# Floppy_Shield.net
KiCad netlist of a schematic drawn in EAGLE
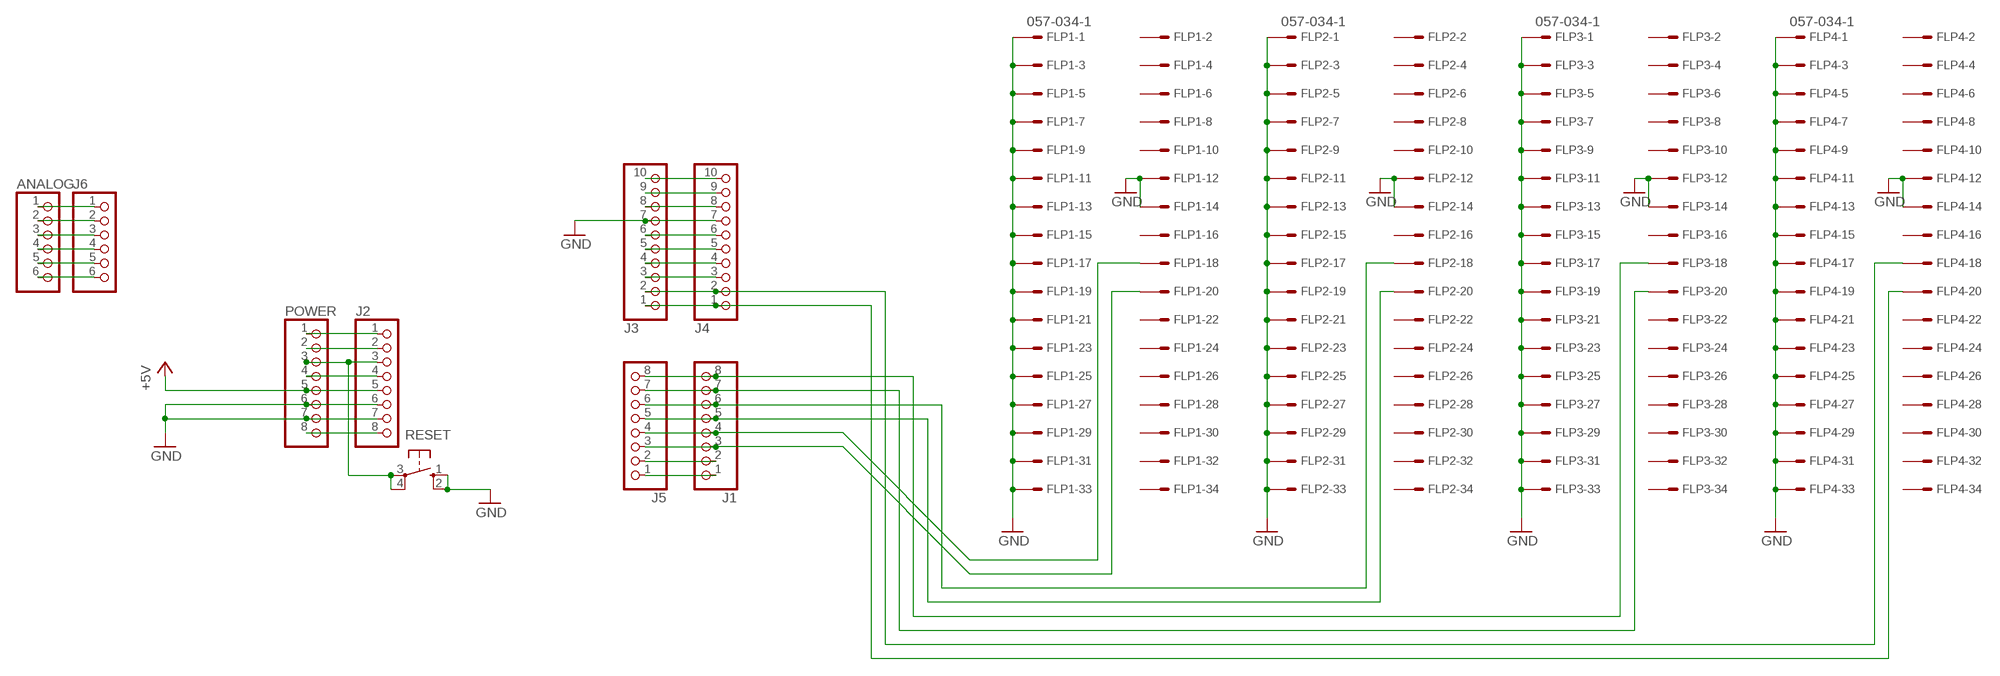
[diagram p0: schematic, sheet 1]

(export (version "E")
  (design (tool "Eeschema 10.0.6"))
  (components
    (comp (ref "ANALOG")
      (value "PINHD-1X6")
      (footprint "eagle-import:1X06")
      (libsource (lib "eagle-import") (part "PINHD-1X6"))
    )
    (comp (ref "FLP1")
      (value "057-034-1")
      (footprint "eagle-import:057-034-1")
      (libsource (lib "eagle-import") (part "057-034-1"))
    )
    (comp (ref "FLP2")
      (value "057-034-1")
      (footprint "eagle-import:057-034-1")
      (libsource (lib "eagle-import") (part "057-034-1"))
    )
    (comp (ref "FLP3")
      (value "057-034-1")
      (footprint "eagle-import:057-034-1")
      (libsource (lib "eagle-import") (part "057-034-1"))
    )
    (comp (ref "FLP4")
      (value "057-034-1")
      (footprint "eagle-import:057-034-1")
      (libsource (lib "eagle-import") (part "057-034-1"))
    )
    (comp (ref "J1")
      (value "PINHD-1X8TH")
      (footprint "eagle-import:1X08-TH")
      (libsource (lib "eagle-import") (part "PINHD-1X8TH"))
    )
    (comp (ref "J2")
      (value "PINHD-1X8TH")
      (footprint "eagle-import:1X08-TH")
      (libsource (lib "eagle-import") (part "PINHD-1X8TH"))
    )
    (comp (ref "J3")
      (value "PINHD-1X10TH")
      (footprint "eagle-import:1X10-TH")
      (libsource (lib "eagle-import") (part "PINHD-1X10TH"))
    )
    (comp (ref "J4")
      (value "PINHD-1X10TH")
      (footprint "eagle-import:1X10-TH")
      (libsource (lib "eagle-import") (part "PINHD-1X10TH"))
    )
    (comp (ref "J5")
      (value "PINHD-1X8TH")
      (footprint "eagle-import:1X08-TH")
      (libsource (lib "eagle-import") (part "PINHD-1X8TH"))
    )
    (comp (ref "J6")
      (value "PINHD-1X6")
      (footprint "eagle-import:1X06")
      (libsource (lib "eagle-import") (part "PINHD-1X6"))
    )
    (comp (ref "POWER")
      (value "PINHD-1X8TH")
      (footprint "eagle-import:1X08-TH")
      (libsource (lib "eagle-import") (part "PINHD-1X8TH"))
    )
    (comp (ref "RESET")
      (value "10-XX")
      (footprint "eagle-import:B3F-10XX")
      (libsource (lib "eagle-import") (part "10-XX"))
    )
  )
  (nets
    (net (code "1") (name "+5V") (class "Default")
      (node (ref "J2") (pin "5") (pinfunction "5_5") (pintype "passive"))
      (node (ref "POWER") (pin "5") (pinfunction "5_5") (pintype "passive"))
    )
    (net (code "2") (name "GND") (class "Default")
      (node (ref "FLP1") (pin "1") (pinfunction "S_1") (pintype "passive"))
      (node (ref "FLP1") (pin "11") (pinfunction "S_11") (pintype "passive"))
      (node (ref "FLP1") (pin "12") (pinfunction "S_12") (pintype "passive"))
      (node (ref "FLP1") (pin "13") (pinfunction "S_13") (pintype "passive"))
      (node (ref "FLP1") (pin "14") (pinfunction "S_14") (pintype "passive"))
      (node (ref "FLP1") (pin "15") (pinfunction "S_15") (pintype "passive"))
      (node (ref "FLP1") (pin "17") (pinfunction "S_17") (pintype "passive"))
      (node (ref "FLP1") (pin "19") (pinfunction "S_19") (pintype "passive"))
      (node (ref "FLP1") (pin "21") (pinfunction "S_21") (pintype "passive"))
      (node (ref "FLP1") (pin "23") (pinfunction "S_23") (pintype "passive"))
      (node (ref "FLP1") (pin "25") (pinfunction "S_25") (pintype "passive"))
      (node (ref "FLP1") (pin "27") (pinfunction "S_27") (pintype "passive"))
      (node (ref "FLP1") (pin "29") (pinfunction "S_29") (pintype "passive"))
      (node (ref "FLP1") (pin "3") (pinfunction "S_3") (pintype "passive"))
      (node (ref "FLP1") (pin "31") (pinfunction "S_31") (pintype "passive"))
      (node (ref "FLP1") (pin "33") (pinfunction "S_33") (pintype "passive"))
      (node (ref "FLP1") (pin "5") (pinfunction "S_5") (pintype "passive"))
      (node (ref "FLP1") (pin "7") (pinfunction "S_7") (pintype "passive"))
      (node (ref "FLP1") (pin "9") (pinfunction "S_9") (pintype "passive"))
      (node (ref "FLP2") (pin "1") (pinfunction "S_1") (pintype "passive"))
      (node (ref "FLP2") (pin "11") (pinfunction "S_11") (pintype "passive"))
      (node (ref "FLP2") (pin "12") (pinfunction "S_12") (pintype "passive"))
      (node (ref "FLP2") (pin "13") (pinfunction "S_13") (pintype "passive"))
      (node (ref "FLP2") (pin "14") (pinfunction "S_14") (pintype "passive"))
      (node (ref "FLP2") (pin "15") (pinfunction "S_15") (pintype "passive"))
      (node (ref "FLP2") (pin "17") (pinfunction "S_17") (pintype "passive"))
      (node (ref "FLP2") (pin "19") (pinfunction "S_19") (pintype "passive"))
      (node (ref "FLP2") (pin "21") (pinfunction "S_21") (pintype "passive"))
      (node (ref "FLP2") (pin "23") (pinfunction "S_23") (pintype "passive"))
      (node (ref "FLP2") (pin "25") (pinfunction "S_25") (pintype "passive"))
      (node (ref "FLP2") (pin "27") (pinfunction "S_27") (pintype "passive"))
      (node (ref "FLP2") (pin "29") (pinfunction "S_29") (pintype "passive"))
      (node (ref "FLP2") (pin "3") (pinfunction "S_3") (pintype "passive"))
      (node (ref "FLP2") (pin "31") (pinfunction "S_31") (pintype "passive"))
      (node (ref "FLP2") (pin "33") (pinfunction "S_33") (pintype "passive"))
      (node (ref "FLP2") (pin "5") (pinfunction "S_5") (pintype "passive"))
      (node (ref "FLP2") (pin "7") (pinfunction "S_7") (pintype "passive"))
      (node (ref "FLP2") (pin "9") (pinfunction "S_9") (pintype "passive"))
      (node (ref "FLP3") (pin "1") (pinfunction "S_1") (pintype "passive"))
      (node (ref "FLP3") (pin "11") (pinfunction "S_11") (pintype "passive"))
      (node (ref "FLP3") (pin "12") (pinfunction "S_12") (pintype "passive"))
      (node (ref "FLP3") (pin "13") (pinfunction "S_13") (pintype "passive"))
      (node (ref "FLP3") (pin "14") (pinfunction "S_14") (pintype "passive"))
      (node (ref "FLP3") (pin "15") (pinfunction "S_15") (pintype "passive"))
      (node (ref "FLP3") (pin "17") (pinfunction "S_17") (pintype "passive"))
      (node (ref "FLP3") (pin "19") (pinfunction "S_19") (pintype "passive"))
      (node (ref "FLP3") (pin "21") (pinfunction "S_21") (pintype "passive"))
      (node (ref "FLP3") (pin "23") (pinfunction "S_23") (pintype "passive"))
      (node (ref "FLP3") (pin "25") (pinfunction "S_25") (pintype "passive"))
      (node (ref "FLP3") (pin "27") (pinfunction "S_27") (pintype "passive"))
      (node (ref "FLP3") (pin "29") (pinfunction "S_29") (pintype "passive"))
      (node (ref "FLP3") (pin "3") (pinfunction "S_3") (pintype "passive"))
      (node (ref "FLP3") (pin "31") (pinfunction "S_31") (pintype "passive"))
      (node (ref "FLP3") (pin "33") (pinfunction "S_33") (pintype "passive"))
      (node (ref "FLP3") (pin "5") (pinfunction "S_5") (pintype "passive"))
      (node (ref "FLP3") (pin "7") (pinfunction "S_7") (pintype "passive"))
      (node (ref "FLP3") (pin "9") (pinfunction "S_9") (pintype "passive"))
      (node (ref "FLP4") (pin "1") (pinfunction "S_1") (pintype "passive"))
      (node (ref "FLP4") (pin "11") (pinfunction "S_11") (pintype "passive"))
      (node (ref "FLP4") (pin "12") (pinfunction "S_12") (pintype "passive"))
      (node (ref "FLP4") (pin "13") (pinfunction "S_13") (pintype "passive"))
      (node (ref "FLP4") (pin "14") (pinfunction "S_14") (pintype "passive"))
      (node (ref "FLP4") (pin "15") (pinfunction "S_15") (pintype "passive"))
      (node (ref "FLP4") (pin "17") (pinfunction "S_17") (pintype "passive"))
      (node (ref "FLP4") (pin "19") (pinfunction "S_19") (pintype "passive"))
      (node (ref "FLP4") (pin "21") (pinfunction "S_21") (pintype "passive"))
      (node (ref "FLP4") (pin "23") (pinfunction "S_23") (pintype "passive"))
      (node (ref "FLP4") (pin "25") (pinfunction "S_25") (pintype "passive"))
      (node (ref "FLP4") (pin "27") (pinfunction "S_27") (pintype "passive"))
      (node (ref "FLP4") (pin "29") (pinfunction "S_29") (pintype "passive"))
      (node (ref "FLP4") (pin "3") (pinfunction "S_3") (pintype "passive"))
      (node (ref "FLP4") (pin "31") (pinfunction "S_31") (pintype "passive"))
      (node (ref "FLP4") (pin "33") (pinfunction "S_33") (pintype "passive"))
      (node (ref "FLP4") (pin "5") (pinfunction "S_5") (pintype "passive"))
      (node (ref "FLP4") (pin "7") (pinfunction "S_7") (pintype "passive"))
      (node (ref "FLP4") (pin "9") (pinfunction "S_9") (pintype "passive"))
      (node (ref "J2") (pin "6") (pinfunction "6_6") (pintype "passive"))
      (node (ref "J2") (pin "7") (pinfunction "7_7") (pintype "passive"))
      (node (ref "J3") (pin "7") (pinfunction "7_7") (pintype "passive"))
      (node (ref "J4") (pin "7") (pinfunction "7_7") (pintype "passive"))
      (node (ref "POWER") (pin "6") (pinfunction "6_6") (pintype "passive"))
      (node (ref "POWER") (pin "7") (pinfunction "7_7") (pintype "passive"))
      (node (ref "RESET") (pin "1") (pinfunction "S_1") (pintype "passive"))
      (node (ref "RESET") (pin "2") (pinfunction "S1_2") (pintype "passive"))
    )
    (net (code "3") (name "Net-(ANALOG-Pad1)") (class "Default")
      (node (ref "ANALOG") (pin "1") (pinfunction "1_1") (pintype "passive"))
      (node (ref "J6") (pin "1") (pinfunction "1_1") (pintype "passive"))
    )
    (net (code "4") (name "Net-(ANALOG-Pad2)") (class "Default")
      (node (ref "ANALOG") (pin "2") (pinfunction "2_2") (pintype "passive"))
      (node (ref "J6") (pin "2") (pinfunction "2_2") (pintype "passive"))
    )
    (net (code "5") (name "Net-(ANALOG-Pad3)") (class "Default")
      (node (ref "ANALOG") (pin "3") (pinfunction "3_3") (pintype "passive"))
      (node (ref "J6") (pin "3") (pinfunction "3_3") (pintype "passive"))
    )
    (net (code "6") (name "Net-(ANALOG-Pad4)") (class "Default")
      (node (ref "ANALOG") (pin "4") (pinfunction "4_4") (pintype "passive"))
      (node (ref "J6") (pin "4") (pinfunction "4_4") (pintype "passive"))
    )
    (net (code "7") (name "Net-(ANALOG-Pad5)") (class "Default")
      (node (ref "ANALOG") (pin "5") (pinfunction "5_5") (pintype "passive"))
      (node (ref "J6") (pin "5") (pinfunction "5_5") (pintype "passive"))
    )
    (net (code "8") (name "Net-(ANALOG-Pad6)") (class "Default")
      (node (ref "ANALOG") (pin "6") (pinfunction "6_6") (pintype "passive"))
      (node (ref "J6") (pin "6") (pinfunction "6_6") (pintype "passive"))
    )
    (net (code "9") (name "Net-(FLP1J-S)") (class "Default")
      (node (ref "FLP1") (pin "18") (pinfunction "S_18") (pintype "passive"))
      (node (ref "J1") (pin "4") (pinfunction "4_4") (pintype "passive"))
      (node (ref "J5") (pin "4") (pinfunction "4_4") (pintype "passive"))
    )
    (net (code "10") (name "Net-(FLP1M-S)") (class "Default")
      (node (ref "FLP1") (pin "20") (pinfunction "S_20") (pintype "passive"))
      (node (ref "J1") (pin "3") (pinfunction "3_3") (pintype "passive"))
      (node (ref "J5") (pin "3") (pinfunction "3_3") (pintype "passive"))
    )
    (net (code "11") (name "Net-(FLP2J-S)") (class "Default")
      (node (ref "FLP2") (pin "18") (pinfunction "S_18") (pintype "passive"))
      (node (ref "J1") (pin "6") (pinfunction "6_6") (pintype "passive"))
      (node (ref "J5") (pin "6") (pinfunction "6_6") (pintype "passive"))
    )
    (net (code "12") (name "Net-(FLP2M-S)") (class "Default")
      (node (ref "FLP2") (pin "20") (pinfunction "S_20") (pintype "passive"))
      (node (ref "J1") (pin "5") (pinfunction "5_5") (pintype "passive"))
      (node (ref "J5") (pin "5") (pinfunction "5_5") (pintype "passive"))
    )
    (net (code "13") (name "Net-(FLP3J-S)") (class "Default")
      (node (ref "FLP3") (pin "18") (pinfunction "S_18") (pintype "passive"))
      (node (ref "J1") (pin "8") (pinfunction "8_8") (pintype "passive"))
      (node (ref "J5") (pin "8") (pinfunction "8_8") (pintype "passive"))
    )
    (net (code "14") (name "Net-(FLP3M-S)") (class "Default")
      (node (ref "FLP3") (pin "20") (pinfunction "S_20") (pintype "passive"))
      (node (ref "J1") (pin "7") (pinfunction "7_7") (pintype "passive"))
      (node (ref "J5") (pin "7") (pinfunction "7_7") (pintype "passive"))
    )
    (net (code "15") (name "Net-(FLP4J-S)") (class "Default")
      (node (ref "FLP4") (pin "18") (pinfunction "S_18") (pintype "passive"))
      (node (ref "J3") (pin "2") (pinfunction "2_2") (pintype "passive"))
      (node (ref "J4") (pin "2") (pinfunction "2_2") (pintype "passive"))
    )
    (net (code "16") (name "Net-(FLP4M-S)") (class "Default")
      (node (ref "FLP4") (pin "20") (pinfunction "S_20") (pintype "passive"))
      (node (ref "J3") (pin "1") (pinfunction "1_1") (pintype "passive"))
      (node (ref "J4") (pin "1") (pinfunction "1_1") (pintype "passive"))
    )
    (net (code "17") (name "Net-(J1-Pad1)") (class "Default")
      (node (ref "J1") (pin "1") (pinfunction "1_1") (pintype "passive"))
      (node (ref "J5") (pin "1") (pinfunction "1_1") (pintype "passive"))
    )
    (net (code "18") (name "Net-(J1-Pad2)") (class "Default")
      (node (ref "J1") (pin "2") (pinfunction "2_2") (pintype "passive"))
      (node (ref "J5") (pin "2") (pinfunction "2_2") (pintype "passive"))
    )
    (net (code "19") (name "Net-(J2-Pad1)") (class "Default")
      (node (ref "J2") (pin "1") (pinfunction "1_1") (pintype "passive"))
      (node (ref "POWER") (pin "1") (pinfunction "1_1") (pintype "passive"))
    )
    (net (code "20") (name "Net-(J2-Pad2)") (class "Default")
      (node (ref "J2") (pin "2") (pinfunction "2_2") (pintype "passive"))
      (node (ref "POWER") (pin "2") (pinfunction "2_2") (pintype "passive"))
    )
    (net (code "21") (name "Net-(J2-Pad4)") (class "Default")
      (node (ref "J2") (pin "4") (pinfunction "4_4") (pintype "passive"))
      (node (ref "POWER") (pin "4") (pinfunction "4_4") (pintype "passive"))
    )
    (net (code "22") (name "Net-(J2-Pad8)") (class "Default")
      (node (ref "J2") (pin "8") (pinfunction "8_8") (pintype "passive"))
      (node (ref "POWER") (pin "8") (pinfunction "8_8") (pintype "passive"))
    )
    (net (code "23") (name "Net-(J3-Pad3)") (class "Default")
      (node (ref "J3") (pin "3") (pinfunction "3_3") (pintype "passive"))
      (node (ref "J4") (pin "3") (pinfunction "3_3") (pintype "passive"))
    )
    (net (code "24") (name "Net-(J3-Pad4)") (class "Default")
      (node (ref "J3") (pin "4") (pinfunction "4_4") (pintype "passive"))
      (node (ref "J4") (pin "4") (pinfunction "4_4") (pintype "passive"))
    )
    (net (code "25") (name "Net-(J3-Pad5)") (class "Default")
      (node (ref "J3") (pin "5") (pinfunction "5_5") (pintype "passive"))
      (node (ref "J4") (pin "5") (pinfunction "5_5") (pintype "passive"))
    )
    (net (code "26") (name "Net-(J3-Pad6)") (class "Default")
      (node (ref "J3") (pin "6") (pinfunction "6_6") (pintype "passive"))
      (node (ref "J4") (pin "6") (pinfunction "6_6") (pintype "passive"))
    )
    (net (code "27") (name "Net-(J3-Pad8)") (class "Default")
      (node (ref "J3") (pin "8") (pinfunction "8_8") (pintype "passive"))
      (node (ref "J4") (pin "8") (pinfunction "8_8") (pintype "passive"))
    )
    (net (code "28") (name "Net-(J3-Pad9)") (class "Default")
      (node (ref "J3") (pin "9") (pinfunction "9_9") (pintype "passive"))
      (node (ref "J4") (pin "9") (pinfunction "9_9") (pintype "passive"))
    )
    (net (code "29") (name "Net-(J3-Pad10)") (class "Default")
      (node (ref "J3") (pin "10") (pinfunction "10_10") (pintype "passive"))
      (node (ref "J4") (pin "10") (pinfunction "10_10") (pintype "passive"))
    )
    (net (code "30") (name "Net-(RESET-P)") (class "Default")
      (node (ref "J2") (pin "3") (pinfunction "3_3") (pintype "passive"))
      (node (ref "POWER") (pin "3") (pinfunction "3_3") (pintype "passive"))
      (node (ref "RESET") (pin "3") (pinfunction "P_3") (pintype "passive"))
      (node (ref "RESET") (pin "4") (pinfunction "P1_4") (pintype "passive"))
    )
    (net (code "31") (name "unconnected-(FLP1AB-S-Pad34)") (class "Default")
      (node (ref "FLP1") (pin "34") (pinfunction "S_34") (pintype "passive"))
    )
    (net (code "32") (name "unconnected-(FLP1AC-S-Pad4)") (class "Default")
      (node (ref "FLP1") (pin "4") (pinfunction "S_4") (pintype "passive"))
    )
    (net (code "33") (name "unconnected-(FLP1AE-S-Pad6)") (class "Default")
      (node (ref "FLP1") (pin "6") (pinfunction "S_6") (pintype "passive"))
    )
    (net (code "34") (name "unconnected-(FLP1AG-S-Pad8)") (class "Default")
      (node (ref "FLP1") (pin "8") (pinfunction "S_8") (pintype "passive"))
    )
    (net (code "35") (name "unconnected-(FLP1B-S-Pad10)") (class "Default")
      (node (ref "FLP1") (pin "10") (pinfunction "S_10") (pintype "passive"))
    )
    (net (code "36") (name "unconnected-(FLP1H-S-Pad16)") (class "Default")
      (node (ref "FLP1") (pin "16") (pinfunction "S_16") (pintype "passive"))
    )
    (net (code "37") (name "unconnected-(FLP1L-S-Pad2)") (class "Default")
      (node (ref "FLP1") (pin "2") (pinfunction "S_2") (pintype "passive"))
    )
    (net (code "38") (name "unconnected-(FLP1O-S-Pad22)") (class "Default")
      (node (ref "FLP1") (pin "22") (pinfunction "S_22") (pintype "passive"))
    )
    (net (code "39") (name "unconnected-(FLP1Q-S-Pad24)") (class "Default")
      (node (ref "FLP1") (pin "24") (pinfunction "S_24") (pintype "passive"))
    )
    (net (code "40") (name "unconnected-(FLP1S-S-Pad26)") (class "Default")
      (node (ref "FLP1") (pin "26") (pinfunction "S_26") (pintype "passive"))
    )
    (net (code "41") (name "unconnected-(FLP1U-S-Pad28)") (class "Default")
      (node (ref "FLP1") (pin "28") (pinfunction "S_28") (pintype "passive"))
    )
    (net (code "42") (name "unconnected-(FLP1X-S-Pad30)") (class "Default")
      (node (ref "FLP1") (pin "30") (pinfunction "S_30") (pintype "passive"))
    )
    (net (code "43") (name "unconnected-(FLP1Z-S-Pad32)") (class "Default")
      (node (ref "FLP1") (pin "32") (pinfunction "S_32") (pintype "passive"))
    )
    (net (code "44") (name "unconnected-(FLP2AB-S-Pad34)") (class "Default")
      (node (ref "FLP2") (pin "34") (pinfunction "S_34") (pintype "passive"))
    )
    (net (code "45") (name "unconnected-(FLP2AC-S-Pad4)") (class "Default")
      (node (ref "FLP2") (pin "4") (pinfunction "S_4") (pintype "passive"))
    )
    (net (code "46") (name "unconnected-(FLP2AE-S-Pad6)") (class "Default")
      (node (ref "FLP2") (pin "6") (pinfunction "S_6") (pintype "passive"))
    )
    (net (code "47") (name "unconnected-(FLP2AG-S-Pad8)") (class "Default")
      (node (ref "FLP2") (pin "8") (pinfunction "S_8") (pintype "passive"))
    )
    (net (code "48") (name "unconnected-(FLP2B-S-Pad10)") (class "Default")
      (node (ref "FLP2") (pin "10") (pinfunction "S_10") (pintype "passive"))
    )
    (net (code "49") (name "unconnected-(FLP2H-S-Pad16)") (class "Default")
      (node (ref "FLP2") (pin "16") (pinfunction "S_16") (pintype "passive"))
    )
    (net (code "50") (name "unconnected-(FLP2L-S-Pad2)") (class "Default")
      (node (ref "FLP2") (pin "2") (pinfunction "S_2") (pintype "passive"))
    )
    (net (code "51") (name "unconnected-(FLP2O-S-Pad22)") (class "Default")
      (node (ref "FLP2") (pin "22") (pinfunction "S_22") (pintype "passive"))
    )
    (net (code "52") (name "unconnected-(FLP2Q-S-Pad24)") (class "Default")
      (node (ref "FLP2") (pin "24") (pinfunction "S_24") (pintype "passive"))
    )
    (net (code "53") (name "unconnected-(FLP2S-S-Pad26)") (class "Default")
      (node (ref "FLP2") (pin "26") (pinfunction "S_26") (pintype "passive"))
    )
    (net (code "54") (name "unconnected-(FLP2U-S-Pad28)") (class "Default")
      (node (ref "FLP2") (pin "28") (pinfunction "S_28") (pintype "passive"))
    )
    (net (code "55") (name "unconnected-(FLP2X-S-Pad30)") (class "Default")
      (node (ref "FLP2") (pin "30") (pinfunction "S_30") (pintype "passive"))
    )
    (net (code "56") (name "unconnected-(FLP2Z-S-Pad32)") (class "Default")
      (node (ref "FLP2") (pin "32") (pinfunction "S_32") (pintype "passive"))
    )
    (net (code "57") (name "unconnected-(FLP3AB-S-Pad34)") (class "Default")
      (node (ref "FLP3") (pin "34") (pinfunction "S_34") (pintype "passive"))
    )
    (net (code "58") (name "unconnected-(FLP3AC-S-Pad4)") (class "Default")
      (node (ref "FLP3") (pin "4") (pinfunction "S_4") (pintype "passive"))
    )
    (net (code "59") (name "unconnected-(FLP3AE-S-Pad6)") (class "Default")
      (node (ref "FLP3") (pin "6") (pinfunction "S_6") (pintype "passive"))
    )
    (net (code "60") (name "unconnected-(FLP3AG-S-Pad8)") (class "Default")
      (node (ref "FLP3") (pin "8") (pinfunction "S_8") (pintype "passive"))
    )
    (net (code "61") (name "unconnected-(FLP3B-S-Pad10)") (class "Default")
      (node (ref "FLP3") (pin "10") (pinfunction "S_10") (pintype "passive"))
    )
    (net (code "62") (name "unconnected-(FLP3H-S-Pad16)") (class "Default")
      (node (ref "FLP3") (pin "16") (pinfunction "S_16") (pintype "passive"))
    )
    (net (code "63") (name "unconnected-(FLP3L-S-Pad2)") (class "Default")
      (node (ref "FLP3") (pin "2") (pinfunction "S_2") (pintype "passive"))
    )
    (net (code "64") (name "unconnected-(FLP3O-S-Pad22)") (class "Default")
      (node (ref "FLP3") (pin "22") (pinfunction "S_22") (pintype "passive"))
    )
    (net (code "65") (name "unconnected-(FLP3Q-S-Pad24)") (class "Default")
      (node (ref "FLP3") (pin "24") (pinfunction "S_24") (pintype "passive"))
    )
    (net (code "66") (name "unconnected-(FLP3S-S-Pad26)") (class "Default")
      (node (ref "FLP3") (pin "26") (pinfunction "S_26") (pintype "passive"))
    )
    (net (code "67") (name "unconnected-(FLP3U-S-Pad28)") (class "Default")
      (node (ref "FLP3") (pin "28") (pinfunction "S_28") (pintype "passive"))
    )
    (net (code "68") (name "unconnected-(FLP3X-S-Pad30)") (class "Default")
      (node (ref "FLP3") (pin "30") (pinfunction "S_30") (pintype "passive"))
    )
    (net (code "69") (name "unconnected-(FLP3Z-S-Pad32)") (class "Default")
      (node (ref "FLP3") (pin "32") (pinfunction "S_32") (pintype "passive"))
    )
    (net (code "70") (name "unconnected-(FLP4AB-S-Pad34)") (class "Default")
      (node (ref "FLP4") (pin "34") (pinfunction "S_34") (pintype "passive"))
    )
    (net (code "71") (name "unconnected-(FLP4AC-S-Pad4)") (class "Default")
      (node (ref "FLP4") (pin "4") (pinfunction "S_4") (pintype "passive"))
    )
    (net (code "72") (name "unconnected-(FLP4AE-S-Pad6)") (class "Default")
      (node (ref "FLP4") (pin "6") (pinfunction "S_6") (pintype "passive"))
    )
    (net (code "73") (name "unconnected-(FLP4AG-S-Pad8)") (class "Default")
      (node (ref "FLP4") (pin "8") (pinfunction "S_8") (pintype "passive"))
    )
    (net (code "74") (name "unconnected-(FLP4B-S-Pad10)") (class "Default")
      (node (ref "FLP4") (pin "10") (pinfunction "S_10") (pintype "passive"))
    )
    (net (code "75") (name "unconnected-(FLP4H-S-Pad16)") (class "Default")
      (node (ref "FLP4") (pin "16") (pinfunction "S_16") (pintype "passive"))
    )
    (net (code "76") (name "unconnected-(FLP4L-S-Pad2)") (class "Default")
      (node (ref "FLP4") (pin "2") (pinfunction "S_2") (pintype "passive"))
    )
    (net (code "77") (name "unconnected-(FLP4O-S-Pad22)") (class "Default")
      (node (ref "FLP4") (pin "22") (pinfunction "S_22") (pintype "passive"))
    )
    (net (code "78") (name "unconnected-(FLP4Q-S-Pad24)") (class "Default")
      (node (ref "FLP4") (pin "24") (pinfunction "S_24") (pintype "passive"))
    )
    (net (code "79") (name "unconnected-(FLP4S-S-Pad26)") (class "Default")
      (node (ref "FLP4") (pin "26") (pinfunction "S_26") (pintype "passive"))
    )
    (net (code "80") (name "unconnected-(FLP4U-S-Pad28)") (class "Default")
      (node (ref "FLP4") (pin "28") (pinfunction "S_28") (pintype "passive"))
    )
    (net (code "81") (name "unconnected-(FLP4X-S-Pad30)") (class "Default")
      (node (ref "FLP4") (pin "30") (pinfunction "S_30") (pintype "passive"))
    )
    (net (code "82") (name "unconnected-(FLP4Z-S-Pad32)") (class "Default")
      (node (ref "FLP4") (pin "32") (pinfunction "S_32") (pintype "passive"))
    )
  )
)
